# 26-XDS110_DEBUGGER.net
KiCad netlist of a schematic drawn in Altium Designer
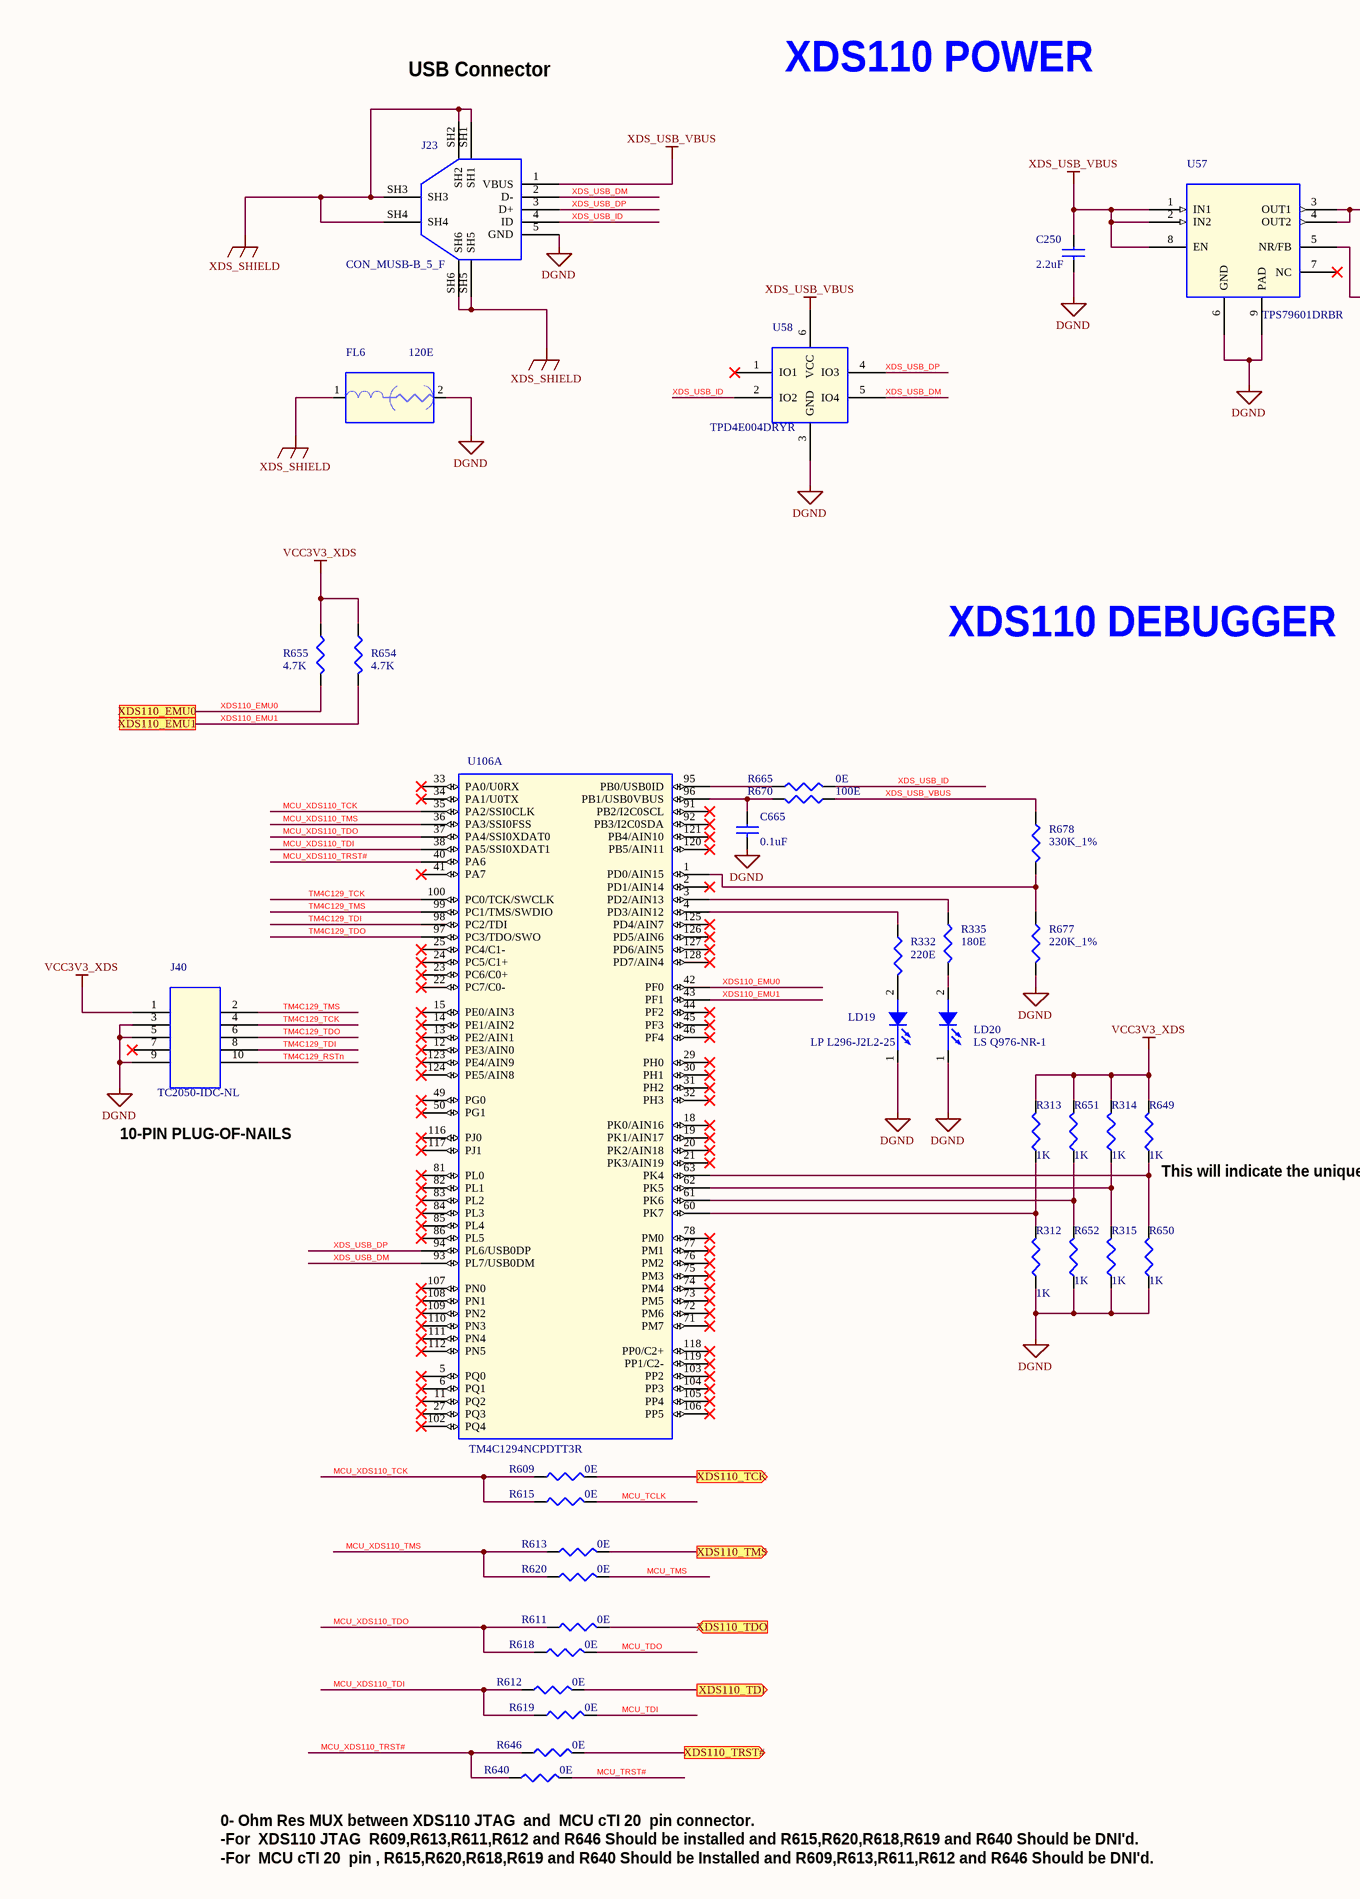
[diagram p0: 26-XDS110 DEBUGGER.SchDoc, left]
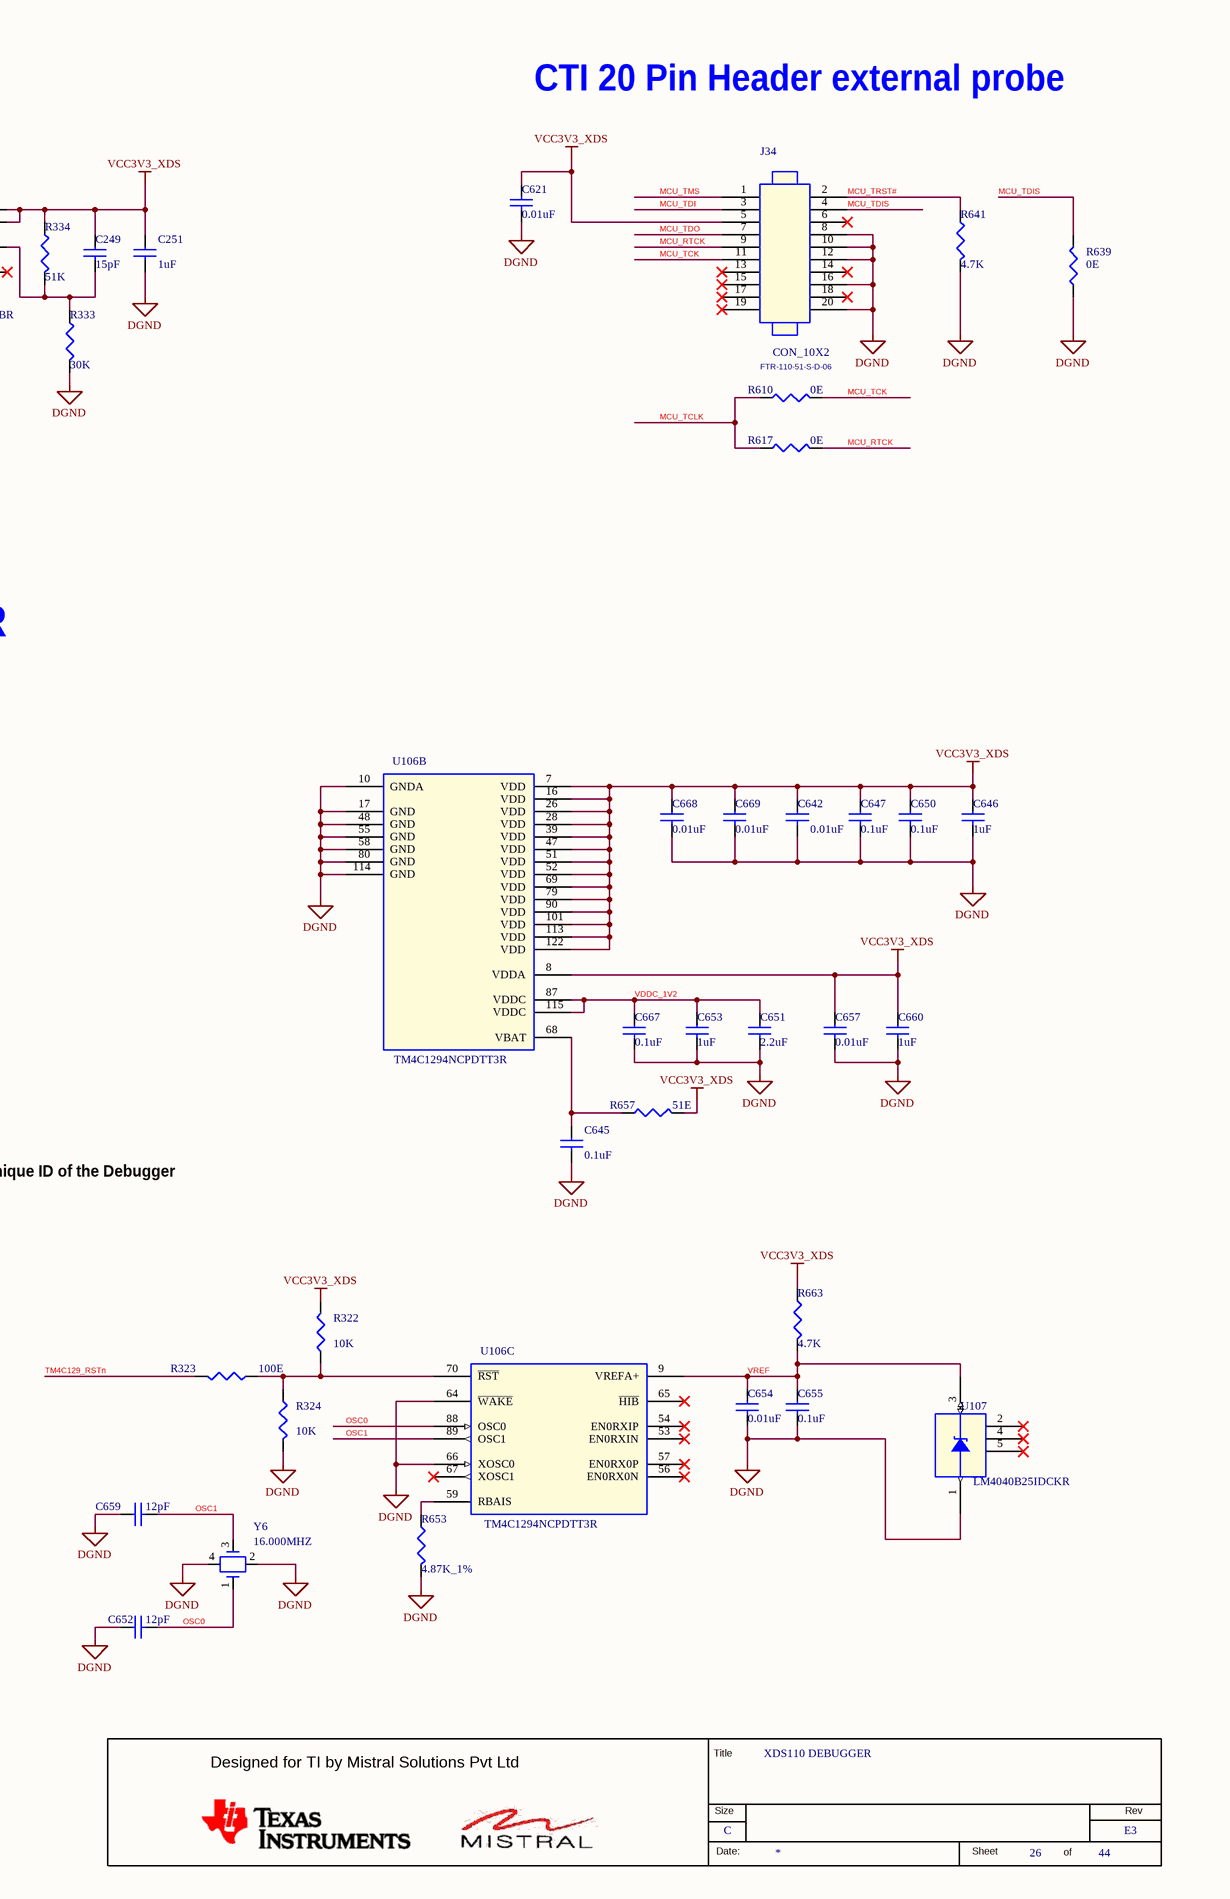
[diagram p1: 26-XDS110 DEBUGGER.SchDoc, right]

(export (version "E")
  (design (tool "Eeschema 10.0.6"))
  (components
    (comp (ref "C249")
      (value "15pF")
      (footprint "CAP0402_0-75")
      (description "CAP CERAMIC 15pF 50V 5% C0G 0402")
      (fields
        (field (name "MISTRAL PART NO") "120010040006-R")
        (field (name "MFR_PART_NUMBER") "GRM1555C1H150JA01D")
      )
      (libsource (lib "*") (part "CAP_Dup5"))
    )
    (comp (ref "C250")
      (value "2.2uF")
      (footprint "CAP0402_0-75")
      (description "CAP CERAMIC 2.2uF 10V 20% X5R 0402")
      (fields
        (field (name "MISTRAL PART NO") "120018010016-R")
        (field (name "MFR_PART_NUMBER") "GRT155R61A225ME01D")
      )
      (libsource (lib "*") (part "CAP_Dup5"))
    )
    (comp (ref "C251")
      (value "1uF")
      (footprint "CAP0402_0-75")
      (description "CAP CERAMIC 1uF 16V 20% X5R 0402")
      (fields (field (name "DISTRIBUTOR_PART_NUMBER") "587-5514-1-ND") (field (name "VOLTAGE") "16V"))
      (libsource (lib "*") (part "CAP_Dup5"))
    )
    (comp (ref "C621")
      (value "0.01uF")
      (footprint "CAP0201_0-5")
      (description "CAP CERAMIC 0.01uF 25V 10% X5R 0201")
      (fields
        (field (name "MISTRAL PART NO") "120018010007-R")
        (field (name "MFR_PART_NUMBER") "GRM033R61E103KA12J")
      )
      (libsource (lib "*") (part "CAP_Dup4"))
    )
    (comp (ref "C642")
      (value "0.01uF")
      (footprint "CAP0201_0-5")
      (description "CAP CERAMIC 0.01uF 25V 10% X5R 0201")
      (fields
        (field (name "MISTRAL PART NO") "120018010007-R")
        (field (name "MFR_PART_NUMBER") "GRM033R61E103KA12J")
      )
      (libsource (lib "*") (part "CAP_Dup5"))
    )
    (comp (ref "C645")
      (value "0.1uF")
      (footprint "CAP0201_0-5")
      (description "CAP CERAMIC 0.1uF 16V 10% X5R 0201")
      (fields (field (name "DISTRIBUTOR_PART_NUMBER") "490-16742-1-ND") (field (name "VOLTAGE") "16V"))
      (libsource (lib "*") (part "CAP_Dup5"))
    )
    (comp (ref "C646")
      (value "1uF")
      (footprint "CAP0402_0-75")
      (description "CAP CERAMIC 1uF 16V 20% X5R 0402")
      (fields
        (field (name "MISTRAL PART NO") "120018020006-R")
        (field (name "MFR_PART_NUMBER") "EMK105BJ105MV-F")
      )
      (libsource (lib "*") (part "CAP_Dup5"))
    )
    (comp (ref "C647")
      (value "0.1uF")
      (footprint "CAP0201_0-5")
      (description "CAP CERAMIC 0.1uF 16V 10% X5R 0201")
      (fields (field (name "DISTRIBUTOR_PART_NUMBER") "490-16742-1-ND") (field (name "VOLTAGE") "16V"))
      (libsource (lib "*") (part "CAP_Dup5"))
    )
    (comp (ref "C650")
      (value "0.1uF")
      (footprint "CAP0201_0-5")
      (description "CAP CERAMIC 0.1uF 16V 10% X5R 0201")
      (fields (field (name "DISTRIBUTOR_PART_NUMBER") "490-16742-1-ND") (field (name "VOLTAGE") "16V"))
      (libsource (lib "*") (part "CAP_Dup5"))
    )
    (comp (ref "C651")
      (value "2.2uF")
      (footprint "CAP0402_0-75")
      (description "CAP CERAMIC 2.2uF 10V 20% X5R 0402")
      (fields
        (field (name "MISTRAL PART NO") "120018010016-R")
        (field (name "MFR_PART_NUMBER") "GRT155R61A225ME01D")
      )
      (libsource (lib "*") (part "CAP_Dup5"))
    )
    (comp (ref "C652")
      (value "12pF")
      (footprint "CAP0402")
      (description "CAP CERAMIC 12pF 50V 5% C0G 0402")
      (fields
        (field (name "MISTRAL PART NO") "120015110024-R")
        (field (name "MFR_PART_NUMBER") "GRM1555C1H120JA01D")
      )
      (libsource (lib "*") (part "CAP_Dup5"))
    )
    (comp (ref "C653")
      (value "1uF")
      (footprint "CAP0402_0-75")
      (description "CAP CERAMIC 1uF 16V 20% X5R 0402")
      (fields (field (name "DISTRIBUTOR_PART_NUMBER") "587-5514-1-ND") (field (name "VOLTAGE") "16V"))
      (libsource (lib "*") (part "CAP_Dup5"))
    )
    (comp (ref "C654")
      (value "0.01uF")
      (footprint "CAP0201_0-5")
      (description "CAP CERAMIC 0.01uF 25V 10% X5R 0201")
      (fields (field (name "DISTRIBUTOR_PART_NUMBER") "GRM033R61E103KA12J-ND") (field (name "VOLTAGE") "25V"))
      (libsource (lib "*") (part "CAP_Dup5"))
    )
    (comp (ref "C655")
      (value "0.1uF")
      (footprint "CAP0201_0-5")
      (description "CAP CERAMIC 0.1uF 16V 10% X5R 0201")
      (fields
        (field (name "MISTRAL PART NO") "120009030072-R")
        (field (name "MFR_PART_NUMBER") "GRM033R61C104KE84J")
      )
      (libsource (lib "*") (part "CAP_Dup5"))
    )
    (comp (ref "C657")
      (value "0.01uF")
      (footprint "CAP0201_0-5")
      (description "CAP CERAMIC 0.01uF 25V 10% X5R 0201")
      (fields (field (name "DISTRIBUTOR_PART_NUMBER") "GRM033R61E103KA12J-ND") (field (name "VOLTAGE") "25V"))
      (libsource (lib "*") (part "CAP_Dup5"))
    )
    (comp (ref "C659")
      (value "12pF")
      (footprint "CAP0402")
      (description "CAP CERAMIC 12pF 50V 5% C0G 0402")
      (fields (field (name "DISTRIBUTOR_PART_NUMBER") "490-5924-1-ND") (field (name "VOLTAGE") "50V"))
      (libsource (lib "*") (part "CAP_Dup5"))
    )
    (comp (ref "C660")
      (value "1uF")
      (footprint "CAP0402_0-75")
      (description "CAP CERAMIC 1uF 16V 20% X5R 0402")
      (fields
        (field (name "MISTRAL PART NO") "120018020006-R")
        (field (name "MFR_PART_NUMBER") "EMK105BJ105MV-F")
      )
      (libsource (lib "*") (part "CAP_Dup5"))
    )
    (comp (ref "C665")
      (value "0.1uF")
      (footprint "CAP0201_0-5")
      (description "CAP CERAMIC 0.1uF 16V 10% X5R 0201")
      (fields (field (name "DISTRIBUTOR_PART_NUMBER") "490-16742-1-ND") (field (name "VOLTAGE") "16V"))
      (libsource (lib "*") (part "CAP_Dup5"))
    )
    (comp (ref "C667")
      (value "0.1uF")
      (footprint "CAP0201_0-5")
      (description "CAP CERAMIC 0.1uF 16V 10% X5R 0201")
      (fields
        (field (name "MISTRAL PART NO") "120009030072-R")
        (field (name "MFR_PART_NUMBER") "GRM033R61C104KE84J")
      )
      (libsource (lib "*") (part "CAP_Dup5"))
    )
    (comp (ref "C668")
      (value "0.01uF")
      (footprint "CAP0201_0-5")
      (description "CAP CERAMIC 0.01uF 25V 10% X5R 0201")
      (fields
        (field (name "MISTRAL PART NO") "120018010007-R")
        (field (name "MFR_PART_NUMBER") "GRM033R61E103KA12J")
      )
      (libsource (lib "*") (part "CAP_Dup5"))
    )
    (comp (ref "C669")
      (value "0.01uF")
      (footprint "CAP0201_0-5")
      (description "CAP CERAMIC 0.01uF 25V 10% X5R 0201")
      (fields (field (name "DISTRIBUTOR_PART_NUMBER") "GRM033R61E103KA12J-ND") (field (name "VOLTAGE") "25V"))
      (libsource (lib "*") (part "CAP_Dup5"))
    )
    (comp (ref "FL6")
      (value "120E")
      (footprint "EMIFIL_BLM15A_0402_0-6")
      (description "FERRITE CHIP 120E 1.3A 0402")
      (fields
        (field (name "MISTRAL PART NO") "130012030043-R")
        (field (name "MFR_PART_NUMBER") "BLM15PD121SN1")
      )
      (libsource (lib "*") (part "EMIFILTER_IND"))
    )
    (comp (ref "J23")
      (value "CON_MUSB-B_5_F")
      (footprint "CON_MUSBB5_1051640001_S_R_S_2-5")
      (description "CON MICRO USB-B TYPE 5POS FEMALE RT SMD")
      (fields (field (name "MISTRAL PART NO") "150017080018-R") (field (name "MFR_PART_NUMBER") "1051640001"))
      (libsource (lib "*") (part "CON_MUSB-B_5_1051640001"))
    )
    (comp (ref "J34")
      (value "CON_10X2")
      (footprint "CON_10X2_FTR-110-51-S-D_P_S_S")
      (description "CON 10X2 1.27MM PITCH MALE SMD")
      (fields
        (field (name "MISTRAL PART NO") "150011090001-R")
        (field (name "MFR_PART_NUMBER") "FTR-110-51-S-D-06")
        (field (name "TOLERANCE") "NA")
      )
      (libsource (lib "*") (part "CON_10X2"))
    )
    (comp (ref "J40")
      (value "TC2050-IDC-NL")
      (footprint "CON_2X5_TC2050-IDC-430-NL_T")
      (description "ACCESSORIE CABLE TAG CONNECT IN CIRCUIT 10POS WITH IDC CONNECTOR")
      (fields (field (name "DISTRIBUTOR_PART_NUMBER") "NA") (field (name "MISTRAL PART NO") "170015120001"))
      (libsource (lib "*") (part "CON_5X2"))
    )
    (comp (ref "LD19")
      (value "LP L296-J2L2-25")
      (footprint "LED_0603_0-7")
      (description "LED PURE GREEN 0603")
      (fields
        (field (name "MISTRAL PART NO") "130017080025-R")
        (field (name "MFR_PART_NUMBER") "LP L296-J2L2-25-Z")
      )
      (libsource (lib "*") (part "DIODE_LED"))
    )
    (comp (ref "LD20")
      (value "LS Q976-NR-1")
      (footprint "LED_0603_0-8")
      (description "LED SUPER RED 0603")
      (fields (field (name "DISTRIBUTOR_PART_NUMBER") "475-2512-1-ND") (field (name "VOLTAGE") "NA"))
      (libsource (lib "*") (part "DIODE_LED"))
    )
    (comp (ref "R312")
      (value "1K")
      (footprint "RES0201")
      (description "RES 1K 1/20W 5% 0201")
      (fields
        (field (name "MISTRAL PART NO") "110015080014-R")
        (field (name "MFR_PART_NUMBER") "CRCW02011K00FKED")
      )
      (libsource (lib "*") (part "RESISTOR_Dup4"))
    )
    (comp (ref "R313")
      (value "1K")
      (footprint "RES0201")
      (description "RES 1K 1/20W 5% 0201")
      (fields (field (name "DISTRIBUTOR_PART_NUMBER") "541-1.00KAABCT-ND") (field (name "VOLTAGE") "NA"))
      (libsource (lib "*") (part "RESISTOR_Dup4"))
    )
    (comp (ref "R314")
      (value "1K")
      (footprint "RES0201")
      (description "RES 1K 1/20W 5% 0201")
      (fields
        (field (name "MISTRAL PART NO") "110015080014-R")
        (field (name "MFR_PART_NUMBER") "CRCW02011K00FKED")
      )
      (libsource (lib "*") (part "RESISTOR_Dup4"))
    )
    (comp (ref "R315")
      (value "1K")
      (footprint "RES0201")
      (description "RES 1K 1/20W 5% 0201")
      (fields (field (name "DISTRIBUTOR_PART_NUMBER") "541-1.00KAABCT-ND") (field (name "VOLTAGE") "NA"))
      (libsource (lib "*") (part "RESISTOR_Dup4"))
    )
    (comp (ref "R322")
      (value "10K")
      (footprint "RES0402_0-5")
      (description "RES 10K 1/16W 5% 0402")
      (fields (field (name "DISTRIBUTOR_PART_NUMBER") "311-10KJRCT-ND") (field (name "VOLTAGE") "NA"))
      (libsource (lib "*") (part "RESISTOR_Dup5"))
    )
    (comp (ref "R323")
      (value "100E")
      (footprint "RES0402_0-5")
      (description "RES 100E 1/16W 5% 0402")
      (fields (field (name "DISTRIBUTOR_PART_NUMBER") "541-100JCT-ND") (field (name "VOLTAGE") "NA"))
      (libsource (lib "*") (part "RESISTOR_Dup5"))
    )
    (comp (ref "R324")
      (value "10K")
      (footprint "RES0402_0-5")
      (description "RES 10K 1/16W 5% 0402")
      (fields
        (field (name "MISTRAL PART NO") "110009030208-R")
        (field (name "MFR_PART_NUMBER") "RC0402JR-0710KL")
      )
      (libsource (lib "*") (part "RESISTOR_Dup5"))
    )
    (comp (ref "R332")
      (value "220E")
      (footprint "RES0402_0-5")
      (description "RES 220E 1/16W 5% 0402")
      (fields (field (name "VOLTAGE") "NA") (field (name "DISTRIBUTOR_PART_NUMBER") "P220JCT-ND"))
      (libsource (lib "*") (part "RESISTOR_Dup5"))
    )
    (comp (ref "R333")
      (value "30K")
      (footprint "RES0402_0-5")
      (description "RES 30K 1/16W 5% 0402")
      (fields
        (field (name "MISTRAL PART NO") "110017080023-R")
        (field (name "MFR_PART_NUMBER") "CRCW040230K0JNED")
      )
      (libsource (lib "*") (part "RESISTOR_Dup5"))
    )
    (comp (ref "R334")
      (value "51K")
      (footprint "RES0402_0-5")
      (description "RES 51K 1/16W 5% 0402")
      (fields
        (field (name "MISTRAL PART NO") "110009030966-R")
        (field (name "MFR_PART_NUMBER") "CRCW040251K0JNED")
      )
      (libsource (lib "*") (part "RESISTOR_Dup5"))
    )
    (comp (ref "R335")
      (value "180E")
      (footprint "RES0402")
      (description "RES 180E 1/16W 5% 0402")
      (fields
        (field (name "MISTRAL PART NO") "110009030371-R")
        (field (name "MFR_PART_NUMBER") "ERJ-2GEJ181X")
      )
      (libsource (lib "*") (part "RESISTOR_Dup5"))
    )
    (comp (ref "R609")
      (value "0E")
      (footprint "RES0402_0-5")
      (description "RES 0E 1/16W 0402")
      (fields (field (name "DISTRIBUTOR_PART_NUMBER") "541-0.0JCT-ND") (field (name "VOLTAGE") "NA"))
      (libsource (lib "*") (part "RESISTOR_Dup4"))
    )
    (comp (ref "R610")
      (value "0E")
      (footprint "RES0402_0-5")
      (description "RES 0E 1/16W 0402")
      (fields (field (name "DISTRIBUTOR_PART_NUMBER") "541-0.0JCT-ND") (field (name "VOLTAGE") "NA"))
      (libsource (lib "*") (part "RESISTOR_Dup4"))
    )
    (comp (ref "R611")
      (value "0E")
      (footprint "RES0402_0-5")
      (description "RES 0E 1/16W 0402")
      (fields
        (field (name "MISTRAL PART NO") "110010080019-P")
        (field (name "MFR_PART_NUMBER") "CRCW04020000Z0ED")
      )
      (libsource (lib "*") (part "RESISTOR_Dup4"))
    )
    (comp (ref "R612")
      (value "0E")
      (footprint "RES0402_0-5")
      (description "RES 0E 1/16W 0402")
      (fields
        (field (name "MISTRAL PART NO") "110010080019-P")
        (field (name "MFR_PART_NUMBER") "CRCW04020000Z0ED")
      )
      (libsource (lib "*") (part "RESISTOR_Dup4"))
    )
    (comp (ref "R613")
      (value "0E")
      (footprint "RES0402_0-5")
      (description "RES 0E 1/16W 0402")
      (fields
        (field (name "MISTRAL PART NO") "110010080019-P")
        (field (name "MFR_PART_NUMBER") "CRCW04020000Z0ED")
      )
      (libsource (lib "*") (part "RESISTOR_Dup4"))
    )
    (comp (ref "R615")
      (value "0E")
      (footprint "RES0402_0-5")
      (description "RES 0E 1/16W 0402")
      (fields (field (name "DISTRIBUTOR_PART_NUMBER") "541-0.0JCT-ND") (field (name "VOLTAGE") "NA"))
      (libsource (lib "*") (part "RESISTOR_Dup4"))
    )
    (comp (ref "R617")
      (value "0E")
      (footprint "RES0402_0-5")
      (description "RES 0E 1/16W 0402")
      (fields
        (field (name "MISTRAL PART NO") "110010080019-P")
        (field (name "MFR_PART_NUMBER") "CRCW04020000Z0ED")
      )
      (libsource (lib "*") (part "RESISTOR_Dup4"))
    )
    (comp (ref "R618")
      (value "0E")
      (footprint "RES0402_0-5")
      (description "RES 0E 1/16W 0402")
      (fields (field (name "DISTRIBUTOR_PART_NUMBER") "541-0.0JCT-ND") (field (name "VOLTAGE") "NA"))
      (libsource (lib "*") (part "RESISTOR_Dup4"))
    )
    (comp (ref "R619")
      (value "0E")
      (footprint "RES0402_0-5")
      (description "RES 0E 1/16W 0402")
      (fields
        (field (name "MISTRAL PART NO") "110010080019-P")
        (field (name "MFR_PART_NUMBER") "CRCW04020000Z0ED")
      )
      (libsource (lib "*") (part "RESISTOR_Dup4"))
    )
    (comp (ref "R620")
      (value "0E")
      (footprint "RES0402_0-5")
      (description "RES 0E 1/16W 0402")
      (fields
        (field (name "MISTRAL PART NO") "110010080019-P")
        (field (name "MFR_PART_NUMBER") "CRCW04020000Z0ED")
      )
      (libsource (lib "*") (part "RESISTOR_Dup4"))
    )
    (comp (ref "R639")
      (value "0E")
      (footprint "RES0402_0-5")
      (description "RES 0E 1/16W 0402")
      (fields
        (field (name "MISTRAL PART NO") "110010080019-P")
        (field (name "MFR_PART_NUMBER") "CRCW04020000Z0ED")
      )
      (libsource (lib "*") (part "RESISTOR_Dup4"))
    )
    (comp (ref "R640")
      (value "0E")
      (footprint "RES0402_0-5")
      (description "RES 0E 1/16W 0402")
      (fields (field (name "DISTRIBUTOR_PART_NUMBER") "541-0.0JCT-ND") (field (name "VOLTAGE") "NA"))
      (libsource (lib "*") (part "RESISTOR_Dup4"))
    )
    (comp (ref "R641")
      (value "4.7K")
      (footprint "RES0402")
      (description "RES 4.7K 1/16W 5% 0402")
      (fields
        (field (name "MISTRAL PART NO") "110009030792-R")
        (field (name "MFR_PART_NUMBER") "RC0402JR-074K7L")
      )
      (libsource (lib "*") (part "RESISTOR_Dup3"))
    )
    (comp (ref "R646")
      (value "0E")
      (footprint "RES0402_0-5")
      (description "RES 0E 1/16W 0402")
      (fields
        (field (name "MISTRAL PART NO") "110010080019-P")
        (field (name "MFR_PART_NUMBER") "CRCW04020000Z0ED")
      )
      (libsource (lib "*") (part "RESISTOR_Dup4"))
    )
    (comp (ref "R649")
      (value "1K")
      (footprint "RES0201")
      (description "RES 1K 1/20W 5% 0201")
      (fields (field (name "DISTRIBUTOR_PART_NUMBER") "541-1.00KAABCT-ND") (field (name "VOLTAGE") "NA"))
      (libsource (lib "*") (part "RESISTOR_Dup4"))
    )
    (comp (ref "R650")
      (value "1K")
      (footprint "RES0201")
      (description "RES 1K 1/20W 5% 0201")
      (fields
        (field (name "MISTRAL PART NO") "110015080014-R")
        (field (name "MFR_PART_NUMBER") "CRCW02011K00FKED")
      )
      (libsource (lib "*") (part "RESISTOR_Dup4"))
    )
    (comp (ref "R651")
      (value "1K")
      (footprint "RES0201")
      (description "RES 1K 1/20W 5% 0201")
      (fields (field (name "DISTRIBUTOR_PART_NUMBER") "541-1.00KAABCT-ND") (field (name "VOLTAGE") "NA"))
      (libsource (lib "*") (part "RESISTOR_Dup4"))
    )
    (comp (ref "R652")
      (value "1K")
      (footprint "RES0201")
      (description "RES 1K 1/20W 5% 0201")
      (fields (field (name "DISTRIBUTOR_PART_NUMBER") "541-1.00KAABCT-ND") (field (name "VOLTAGE") "NA"))
      (libsource (lib "*") (part "RESISTOR_Dup4"))
    )
    (comp (ref "R653")
      (value "4.87K_1%")
      (footprint "RES0402")
      (description "RES 4.87K 1/16W 1% 0402")
      (fields
        (field (name "MISTRAL PART NO") "110009030803-R")
        (field (name "MFR_PART_NUMBER") "ERJ2RKF4871X")
      )
      (libsource (lib "*") (part "RESISTOR_Dup5"))
    )
    (comp (ref "R654")
      (value "4.7K")
      (footprint "RES0402")
      (description "RES 4.7K 1/16W 5% 0402")
      (fields (field (name "DISTRIBUTOR_PART_NUMBER") "311-4.7KJRCT-ND") (field (name "VOLTAGE") "NA"))
      (libsource (lib "*") (part "RESISTOR_Dup3"))
    )
    (comp (ref "R655")
      (value "4.7K")
      (footprint "RES0402")
      (description "RES 4.7K 1/16W 5% 0402")
      (fields
        (field (name "MISTRAL PART NO") "110009030792-R")
        (field (name "MFR_PART_NUMBER") "RC0402JR-074K7L")
      )
      (libsource (lib "*") (part "RESISTOR_Dup3"))
    )
    (comp (ref "R657")
      (value "51E")
      (footprint "RES0402")
      (description "RES 51E 1/16W 5% 0402")
      (fields (field (name "DISTRIBUTOR_PART_NUMBER") "P51JTR-ND") (field (name "TOLERANCE") "5%"))
      (libsource (lib "*") (part "RESISTOR_Dup5"))
    )
    (comp (ref "R663")
      (value "4.7K")
      (footprint "RES0402")
      (description "RES 4.7K 1/16W 5% 0402")
      (fields
        (field (name "MISTRAL PART NO") "110009030792-R")
        (field (name "MFR_PART_NUMBER") "RC0402JR-074K7L")
      )
      (libsource (lib "*") (part "RESISTOR_Dup3"))
    )
    (comp (ref "R665")
      (value "0E")
      (footprint "RES0402_0-5")
      (description "RES 0E 1/16W 0402")
      (fields (field (name "DISTRIBUTOR_PART_NUMBER") "541-0.0JCT-ND") (field (name "VOLTAGE") "NA"))
      (libsource (lib "*") (part "RESISTOR_Dup4"))
    )
    (comp (ref "R670")
      (value "100E")
      (footprint "RES0402_0-5")
      (description "RES 100E 1/16W 5% 0402")
      (fields (field (name "DISTRIBUTOR_PART_NUMBER") "541-100JCT-ND") (field (name "VOLTAGE") "NA"))
      (libsource (lib "*") (part "RESISTOR_Dup5"))
    )
    (comp (ref "R677")
      (value "220K_1%")
      (footprint "RES0402_0-5")
      (description "RES 220K 1/16W 1% 0402")
      (fields (field (name "DISTRIBUTOR_PART_NUMBER") "541-220KLCT-ND") (field (name "VOLTAGE") "NA"))
      (libsource (lib "*") (part "RESISTOR_Dup5"))
    )
    (comp (ref "R678")
      (value "330K_1%")
      (footprint "RES0402_0-5")
      (description "RES 330K 1/16W 1% 0402")
      (fields (field (name "DISTRIBUTOR_PART_NUMBER") "541-330KLCT-ND") (field (name "VOLTAGE") "NA"))
      (libsource (lib "*") (part "RESISTOR_Dup5"))
    )
    (comp (ref "U57")
      (value "TPS79601DRBR")
      (footprint "SON8_25-59_130X130_1")
      (description "IC 1A HIGH PSRR RF ADJ LDO LINEAR REGULATOR SON8")
      (fields
        (field (name "VOLTAGE") "NA")
        (field (name "MISTRAL PART NO") "142009080012-R")
        (field (name "LIBRARY PATH") "Y~{:}MIS_DATABAS~{E}Librar~{y}ALTIUM_TOO~{L}SCHEMATICS_PART~{S}MS_MISCPOWER_Library.schlib")
      )
      (libsource (lib "*") (part "TPS79601DRBR_SON8"))
    )
    (comp (ref "U58")
      (value "TPD4E004DRYR")
      (footprint "SON6_19-68_60X45")
      (description "IC 4CH ESD-PROT ARRAY SON6")
      (fields
        (field (name "MISTRAL PART NO") "141010020012-P")
        (field (name "DISTRIBUTOR_PART_NUMBER") "296-23618-1-ND")
      )
      (libsource (lib "*") (part "TPD4E004_SON6"))
    )
    (comp (ref "U106")
      (value "TM4C1294NCPDTT3R")
      (footprint "TQFP128_15-74_550X550_1-2")
      (description "IC 32-BIT MICROCONTROLLER WITH 1MB FLASH TQFP128")
      (fields
        (field (name "DISTRIBUTOR_PART_NUMBER") "TM4C1294NCPDTT3R-ND")
        (field (name "VOLTAGE") "NA")
        (field (name "MISTRAL PART NO") "141217080002-R")
        (field (name "TOLERANCE") "NA")
      )
      (libsource (lib "*") (part "TM4C1294NCPDTT3R_TQFP128"))
    )
    (comp (ref "U107")
      (value "LM4040B25IDCKR")
      (footprint "SC70-5_1-1")
      (description "IC PRECISION MICROPOWER SHUNT VOLTAGE REFERENCE SC70-5")
      (fields (field (name "DISTRIBUTOR_PART_NUMBER") "296-20873-1-ND") (field (name "VOLTAGE") "NA"))
      (libsource (lib "*") (part "LM4040B25IDCKR_SC70-5"))
    )
    (comp (ref "Y6")
      (value "16.000MHZ")
      (footprint "XTAL4_NX3225GA_130X100_SMD_0-9")
      (description "CRY 16.000MHz SMD")
      (fields
        (field (name "MISTRAL PART NO") "130017080024-R")
        (field (name "MFR_PART_NUMBER") "NX3225GA-16.000M-STD-CRG-1")
      )
      (libsource (lib "*") (part "CRY4_13"))
    )
  )
  (nets
    (net (code "1") (name "/MCU_RTCK") (class "Default")
      (node (ref "J34") (pin "9") (pinfunction "9_9") (pintype "passive"))
      (node (ref "R617") (pin "2") (pinfunction "2_2") (pintype "passive"))
    )
    (net (code "2") (name "/MCU_TCK") (class "Default")
      (node (ref "J34") (pin "11") (pinfunction "11_11") (pintype "passive"))
      (node (ref "R610") (pin "2") (pinfunction "2_2") (pintype "passive"))
    )
    (net (code "3") (name "/MCU_TCLK") (class "Default")
      (node (ref "R610") (pin "1") (pinfunction "1_1") (pintype "passive"))
      (node (ref "R615") (pin "2") (pinfunction "2_2") (pintype "passive"))
      (node (ref "R617") (pin "1") (pinfunction "1_1") (pintype "passive"))
    )
    (net (code "4") (name "/MCU_TDI") (class "Default")
      (node (ref "J34") (pin "3") (pinfunction "3_3") (pintype "passive"))
      (node (ref "R619") (pin "2") (pinfunction "2_2") (pintype "passive"))
    )
    (net (code "5") (name "/MCU_TDIS") (class "Default")
      (node (ref "J34") (pin "4") (pinfunction "4_4") (pintype "passive"))
      (node (ref "R639") (pin "2") (pinfunction "2_2") (pintype "passive"))
    )
    (net (code "6") (name "/MCU_TDO") (class "Default")
      (node (ref "J34") (pin "7") (pinfunction "7_7") (pintype "passive"))
      (node (ref "R618") (pin "2") (pinfunction "2_2") (pintype "passive"))
    )
    (net (code "7") (name "/MCU_TMS") (class "Default")
      (node (ref "J34") (pin "1") (pinfunction "1_1") (pintype "passive"))
      (node (ref "R620") (pin "2") (pinfunction "2_2") (pintype "passive"))
    )
    (net (code "8") (name "/MCU_TRST#") (class "Default")
      (node (ref "J34") (pin "2") (pinfunction "2_2") (pintype "passive"))
      (node (ref "R640") (pin "2") (pinfunction "2_2") (pintype "passive"))
      (node (ref "R641") (pin "1") (pinfunction "1_1") (pintype "passive"))
    )
    (net (code "9") (name "/MCU_XDS110_TCK") (class "Default")
      (node (ref "R609") (pin "1") (pinfunction "1_1") (pintype "passive"))
      (node (ref "R615") (pin "1") (pinfunction "1_1") (pintype "passive"))
      (node (ref "U106") (pin "35") (pinfunction "PA2/SSI0CLK_35") (pintype "bidirectional"))
    )
    (net (code "10") (name "/MCU_XDS110_TDI") (class "Default")
      (node (ref "R612") (pin "1") (pinfunction "1_1") (pintype "passive"))
      (node (ref "R619") (pin "1") (pinfunction "1_1") (pintype "passive"))
      (node (ref "U106") (pin "38") (pinfunction "PA5/SSI0XDAT1_38") (pintype "bidirectional"))
    )
    (net (code "11") (name "/MCU_XDS110_TDO") (class "Default")
      (node (ref "R611") (pin "1") (pinfunction "1_1") (pintype "passive"))
      (node (ref "R618") (pin "1") (pinfunction "1_1") (pintype "passive"))
      (node (ref "U106") (pin "37") (pinfunction "PA4/SSI0XDAT0_37") (pintype "bidirectional"))
    )
    (net (code "12") (name "/MCU_XDS110_TMS") (class "Default")
      (node (ref "R613") (pin "1") (pinfunction "1_1") (pintype "passive"))
      (node (ref "R620") (pin "1") (pinfunction "1_1") (pintype "passive"))
      (node (ref "U106") (pin "36") (pinfunction "PA3/SSI0FSS_36") (pintype "bidirectional"))
    )
    (net (code "13") (name "/MCU_XDS110_TRST#") (class "Default")
      (node (ref "R640") (pin "1") (pinfunction "1_1") (pintype "passive"))
      (node (ref "R646") (pin "1") (pinfunction "1_1") (pintype "passive"))
      (node (ref "U106") (pin "40") (pinfunction "PA6_40") (pintype "bidirectional"))
    )
    (net (code "14") (name "/OSC0") (class "Default")
      (node (ref "C652") (pin "2") (pinfunction "2_2") (pintype "passive"))
      (node (ref "U106") (pin "88") (pinfunction "OSC0_88") (pintype "input"))
      (node (ref "Y6") (pin "1") (pinfunction "1_1") (pintype "passive"))
    )
    (net (code "15") (name "/OSC1") (class "Default")
      (node (ref "C659") (pin "2") (pinfunction "2_2") (pintype "passive"))
      (node (ref "U106") (pin "89") (pinfunction "OSC1_89") (pintype "output"))
      (node (ref "Y6") (pin "3") (pinfunction "3_3") (pintype "passive"))
    )
    (net (code "16") (name "/TM4C129_RSTn") (class "Default")
      (node (ref "J40") (pin "10") (pinfunction "10_10") (pintype "passive"))
      (node (ref "R323") (pin "2") (pinfunction "2_2") (pintype "passive"))
    )
    (net (code "17") (name "/TM4C129_TCK") (class "Default")
      (node (ref "J40") (pin "4") (pinfunction "4_4") (pintype "passive"))
      (node (ref "U106") (pin "100") (pinfunction "PC0/TCK/SWCLK_100") (pintype "bidirectional"))
    )
    (net (code "18") (name "/TM4C129_TDI") (class "Default")
      (node (ref "J40") (pin "8") (pinfunction "8_8") (pintype "passive"))
      (node (ref "U106") (pin "98") (pinfunction "PC2/TDI_98") (pintype "bidirectional"))
    )
    (net (code "19") (name "/TM4C129_TDO") (class "Default")
      (node (ref "J40") (pin "6") (pinfunction "6_6") (pintype "passive"))
      (node (ref "U106") (pin "97") (pinfunction "PC3/TDO/SWO_97") (pintype "bidirectional"))
    )
    (net (code "20") (name "/TM4C129_TMS") (class "Default")
      (node (ref "J40") (pin "2") (pinfunction "2_2") (pintype "passive"))
      (node (ref "U106") (pin "99") (pinfunction "PC1/TMS/SWDIO_99") (pintype "bidirectional"))
    )
    (net (code "21") (name "/VDDC_1V2") (class "Default")
      (node (ref "C651") (pin "1") (pinfunction "1_1") (pintype "passive"))
      (node (ref "C653") (pin "1") (pinfunction "1_1") (pintype "passive"))
      (node (ref "C667") (pin "1") (pinfunction "1_1") (pintype "passive"))
      (node (ref "U106") (pin "115") (pinfunction "VDDC_115") (pintype "power_in"))
      (node (ref "U106") (pin "87") (pinfunction "VDDC_87") (pintype "power_in"))
    )
    (net (code "22") (name "/VREF") (class "Default")
      (node (ref "C654") (pin "1") (pinfunction "1_1") (pintype "passive"))
      (node (ref "C655") (pin "1") (pinfunction "1_1") (pintype "passive"))
      (node (ref "R663") (pin "2") (pinfunction "2_2") (pintype "passive"))
      (node (ref "U106") (pin "9") (pinfunction "VREFA+_9") (pintype "passive"))
      (node (ref "U107") (pin "3") (pinfunction "CATHODE_3") (pintype "bidirectional"))
    )
    (net (code "23") (name "/XDS110_EMU0") (class "Default")
      (node (ref "R655") (pin "2") (pinfunction "2_2") (pintype "passive"))
      (node (ref "U106") (pin "42") (pinfunction "PF0_42") (pintype "bidirectional"))
    )
    (net (code "24") (name "/XDS110_EMU1") (class "Default")
      (node (ref "R654") (pin "2") (pinfunction "2_2") (pintype "passive"))
      (node (ref "U106") (pin "43") (pinfunction "PF1_43") (pintype "bidirectional"))
    )
    (net (code "25") (name "/XDS110_TCK") (class "Default")
      (node (ref "R609") (pin "2") (pinfunction "2_2") (pintype "passive"))
    )
    (net (code "26") (name "/XDS110_TDI") (class "Default")
      (node (ref "R612") (pin "2") (pinfunction "2_2") (pintype "passive"))
    )
    (net (code "27") (name "/XDS110_TDO") (class "Default")
      (node (ref "R611") (pin "2") (pinfunction "2_2") (pintype "passive"))
    )
    (net (code "28") (name "/XDS110_TMS") (class "Default")
      (node (ref "R613") (pin "2") (pinfunction "2_2") (pintype "passive"))
    )
    (net (code "29") (name "/XDS110_TRST#") (class "Default")
      (node (ref "R646") (pin "2") (pinfunction "2_2") (pintype "passive"))
    )
    (net (code "30") (name "/XDS_USB_DM") (class "Default")
      (node (ref "J23") (pin "2") (pinfunction "D-_2") (pintype "passive"))
      (node (ref "U106") (pin "93") (pinfunction "PL7/USB0DM_93") (pintype "bidirectional"))
      (node (ref "U58") (pin "5") (pinfunction "IO4_5") (pintype "passive"))
    )
    (net (code "31") (name "/XDS_USB_DP") (class "Default")
      (node (ref "J23") (pin "3") (pinfunction "D+_3") (pintype "passive"))
      (node (ref "U106") (pin "94") (pinfunction "PL6/USB0DP_94") (pintype "bidirectional"))
      (node (ref "U58") (pin "4") (pinfunction "IO3_4") (pintype "passive"))
    )
    (net (code "32") (name "/XDS_USB_ID") (class "Default")
      (node (ref "J23") (pin "4") (pinfunction "ID_4") (pintype "passive"))
      (node (ref "R665") (pin "2") (pinfunction "2_2") (pintype "passive"))
      (node (ref "U58") (pin "2") (pinfunction "IO2_2") (pintype "passive"))
    )
    (net (code "33") (name "DGND") (class "Default")
      (node (ref "C250") (pin "2") (pinfunction "2_2") (pintype "passive"))
      (node (ref "C251") (pin "2") (pinfunction "2_2") (pintype "passive"))
      (node (ref "C621") (pin "2") (pinfunction "2_2") (pintype "passive"))
      (node (ref "C642") (pin "2") (pinfunction "2_2") (pintype "passive"))
      (node (ref "C645") (pin "2") (pinfunction "2_2") (pintype "passive"))
      (node (ref "C646") (pin "2") (pinfunction "2_2") (pintype "passive"))
      (node (ref "C647") (pin "2") (pinfunction "2_2") (pintype "passive"))
      (node (ref "C650") (pin "2") (pinfunction "2_2") (pintype "passive"))
      (node (ref "C651") (pin "2") (pinfunction "2_2") (pintype "passive"))
      (node (ref "C652") (pin "1") (pinfunction "1_1") (pintype "passive"))
      (node (ref "C653") (pin "2") (pinfunction "2_2") (pintype "passive"))
      (node (ref "C654") (pin "2") (pinfunction "2_2") (pintype "passive"))
      (node (ref "C655") (pin "2") (pinfunction "2_2") (pintype "passive"))
      (node (ref "C657") (pin "2") (pinfunction "2_2") (pintype "passive"))
      (node (ref "C659") (pin "1") (pinfunction "1_1") (pintype "passive"))
      (node (ref "C660") (pin "2") (pinfunction "2_2") (pintype "passive"))
      (node (ref "C665") (pin "2") (pinfunction "2_2") (pintype "passive"))
      (node (ref "C667") (pin "2") (pinfunction "2_2") (pintype "passive"))
      (node (ref "C668") (pin "2") (pinfunction "2_2") (pintype "passive"))
      (node (ref "C669") (pin "2") (pinfunction "2_2") (pintype "passive"))
      (node (ref "FL6") (pin "2") (pinfunction "2_2") (pintype "passive"))
      (node (ref "J23") (pin "5") (pinfunction "GND_5") (pintype "power_in"))
      (node (ref "J34") (pin "10") (pinfunction "10_10") (pintype "passive"))
      (node (ref "J34") (pin "12") (pinfunction "12_12") (pintype "passive"))
      (node (ref "J34") (pin "16") (pinfunction "16_16") (pintype "passive"))
      (node (ref "J34") (pin "20") (pinfunction "20_20") (pintype "passive"))
      (node (ref "J34") (pin "8") (pinfunction "8_8") (pintype "passive"))
      (node (ref "J40") (pin "3") (pinfunction "3_3") (pintype "passive"))
      (node (ref "J40") (pin "5") (pinfunction "5_5") (pintype "passive"))
      (node (ref "J40") (pin "9") (pinfunction "9_9") (pintype "passive"))
      (node (ref "LD19") (pin "1") (pinfunction "CATHODE_1") (pintype "passive"))
      (node (ref "LD20") (pin "1") (pinfunction "CATHODE_1") (pintype "passive"))
      (node (ref "R312") (pin "1") (pinfunction "1_1") (pintype "passive"))
      (node (ref "R315") (pin "1") (pinfunction "1_1") (pintype "passive"))
      (node (ref "R324") (pin "2") (pinfunction "2_2") (pintype "passive"))
      (node (ref "R333") (pin "2") (pinfunction "2_2") (pintype "passive"))
      (node (ref "R639") (pin "1") (pinfunction "1_1") (pintype "passive"))
      (node (ref "R641") (pin "2") (pinfunction "2_2") (pintype "passive"))
      (node (ref "R650") (pin "1") (pinfunction "1_1") (pintype "passive"))
      (node (ref "R652") (pin "1") (pinfunction "1_1") (pintype "passive"))
      (node (ref "R653") (pin "2") (pinfunction "2_2") (pintype "passive"))
      (node (ref "R677") (pin "2") (pinfunction "2_2") (pintype "passive"))
      (node (ref "U106") (pin "10") (pinfunction "GNDA_10") (pintype "power_in"))
      (node (ref "U106") (pin "114") (pinfunction "GND_114") (pintype "power_in"))
      (node (ref "U106") (pin "17") (pinfunction "GND_17") (pintype "power_in"))
      (node (ref "U106") (pin "48") (pinfunction "GND_48") (pintype "power_in"))
      (node (ref "U106") (pin "55") (pinfunction "GND_55") (pintype "power_in"))
      (node (ref "U106") (pin "58") (pinfunction "GND_58") (pintype "power_in"))
      (node (ref "U106") (pin "64") (pinfunction "~{WAKE}_64") (pintype "passive"))
      (node (ref "U106") (pin "66") (pinfunction "XOSC0_66") (pintype "input"))
      (node (ref "U106") (pin "80") (pinfunction "GND_80") (pintype "power_in"))
      (node (ref "U107") (pin "1") (pinfunction "ANODE_1") (pintype "output"))
      (node (ref "U57") (pin "6") (pinfunction "GND_6") (pintype "power_in"))
      (node (ref "U57") (pin "9") (pinfunction "PAD_9") (pintype "power_in"))
      (node (ref "U58") (pin "3") (pinfunction "GND_3") (pintype "power_in"))
      (node (ref "Y6") (pin "2") (pinfunction "2_2") (pintype "passive"))
      (node (ref "Y6") (pin "4") (pinfunction "4_4") (pintype "passive"))
    )
    (net (code "34") (name "Net-(LD19-ANODE)") (class "Default")
      (node (ref "LD19") (pin "2") (pinfunction "ANODE_2") (pintype "passive"))
      (node (ref "R332") (pin "2") (pinfunction "2_2") (pintype "passive"))
    )
    (net (code "35") (name "Net-(LD20-ANODE)") (class "Default")
      (node (ref "LD20") (pin "2") (pinfunction "ANODE_2") (pintype "passive"))
      (node (ref "R335") (pin "2") (pinfunction "2_2") (pintype "passive"))
    )
    (net (code "36") (name "Net-(U57-NR{slash}FB)") (class "Default")
      (node (ref "C249") (pin "2") (pinfunction "2_2") (pintype "passive"))
      (node (ref "R333") (pin "1") (pinfunction "1_1") (pintype "passive"))
      (node (ref "R334") (pin "2") (pinfunction "2_2") (pintype "passive"))
      (node (ref "U57") (pin "5") (pinfunction "NR/FB_5") (pintype "passive"))
    )
    (net (code "37") (name "Net-(U106A-PB0{slash}USB0ID)") (class "Default")
      (node (ref "R665") (pin "1") (pinfunction "1_1") (pintype "passive"))
      (node (ref "U106") (pin "95") (pinfunction "PB0/USB0ID_95") (pintype "bidirectional"))
    )
    (net (code "38") (name "Net-(U106A-PB1{slash}USB0VBUS)") (class "Default")
      (node (ref "C665") (pin "1") (pinfunction "1_1") (pintype "passive"))
      (node (ref "R670") (pin "2") (pinfunction "2_2") (pintype "passive"))
      (node (ref "U106") (pin "96") (pinfunction "PB1/USB0VBUS_96") (pintype "bidirectional"))
    )
    (net (code "39") (name "Net-(U106A-PD0{slash}AIN15)") (class "Default")
      (node (ref "R677") (pin "1") (pinfunction "1_1") (pintype "passive"))
      (node (ref "R678") (pin "2") (pinfunction "2_2") (pintype "passive"))
      (node (ref "U106") (pin "1") (pinfunction "PD0/AIN15_1") (pintype "bidirectional"))
    )
    (net (code "40") (name "Net-(U106A-PD2{slash}AIN13)") (class "Default")
      (node (ref "R335") (pin "1") (pinfunction "1_1") (pintype "passive"))
      (node (ref "U106") (pin "3") (pinfunction "PD2/AIN13_3") (pintype "bidirectional"))
    )
    (net (code "41") (name "Net-(U106A-PD3{slash}AIN12)") (class "Default")
      (node (ref "R332") (pin "1") (pinfunction "1_1") (pintype "passive"))
      (node (ref "U106") (pin "4") (pinfunction "PD3/AIN12_4") (pintype "bidirectional"))
    )
    (net (code "42") (name "Net-(U106A-PK4)") (class "Default")
      (node (ref "R649") (pin "1") (pinfunction "1_1") (pintype "passive"))
      (node (ref "R650") (pin "2") (pinfunction "2_2") (pintype "passive"))
      (node (ref "U106") (pin "63") (pinfunction "PK4_63") (pintype "bidirectional"))
    )
    (net (code "43") (name "Net-(U106A-PK5)") (class "Default")
      (node (ref "R314") (pin "1") (pinfunction "1_1") (pintype "passive"))
      (node (ref "R315") (pin "2") (pinfunction "2_2") (pintype "passive"))
      (node (ref "U106") (pin "62") (pinfunction "PK5_62") (pintype "bidirectional"))
    )
    (net (code "44") (name "Net-(U106A-PK6)") (class "Default")
      (node (ref "R651") (pin "1") (pinfunction "1_1") (pintype "passive"))
      (node (ref "R652") (pin "2") (pinfunction "2_2") (pintype "passive"))
      (node (ref "U106") (pin "61") (pinfunction "PK6_61") (pintype "bidirectional"))
    )
    (net (code "45") (name "Net-(U106A-PK7)") (class "Default")
      (node (ref "R312") (pin "2") (pinfunction "2_2") (pintype "passive"))
      (node (ref "R313") (pin "1") (pinfunction "1_1") (pintype "passive"))
      (node (ref "U106") (pin "60") (pinfunction "PK7_60") (pintype "bidirectional"))
    )
    (net (code "46") (name "Net-(U106B-VBAT)") (class "Default")
      (node (ref "C645") (pin "1") (pinfunction "1_1") (pintype "passive"))
      (node (ref "R657") (pin "1") (pinfunction "1_1") (pintype "passive"))
      (node (ref "U106") (pin "68") (pinfunction "VBAT_68") (pintype "power_in"))
    )
    (net (code "47") (name "Net-(U106C-RBAIS)") (class "Default")
      (node (ref "R653") (pin "1") (pinfunction "1_1") (pintype "passive"))
      (node (ref "U106") (pin "59") (pinfunction "RBAIS_59") (pintype "passive"))
    )
    (net (code "48") (name "Net-(U106C-~{RST})") (class "Default")
      (node (ref "R322") (pin "1") (pinfunction "1_1") (pintype "passive"))
      (node (ref "R323") (pin "1") (pinfunction "1_1") (pintype "passive"))
      (node (ref "R324") (pin "1") (pinfunction "1_1") (pintype "passive"))
      (node (ref "U106") (pin "70") (pinfunction "~{RST}_70") (pintype "passive"))
    )
    (net (code "49") (name "VCC3V3_XDS") (class "Default")
      (node (ref "C249") (pin "1") (pinfunction "1_1") (pintype "passive"))
      (node (ref "C251") (pin "1") (pinfunction "1_1") (pintype "passive"))
      (node (ref "C621") (pin "1") (pinfunction "1_1") (pintype "passive"))
      (node (ref "C642") (pin "1") (pinfunction "1_1") (pintype "passive"))
      (node (ref "C646") (pin "1") (pinfunction "1_1") (pintype "passive"))
      (node (ref "C647") (pin "1") (pinfunction "1_1") (pintype "passive"))
      (node (ref "C650") (pin "1") (pinfunction "1_1") (pintype "passive"))
      (node (ref "C657") (pin "1") (pinfunction "1_1") (pintype "passive"))
      (node (ref "C660") (pin "1") (pinfunction "1_1") (pintype "passive"))
      (node (ref "C668") (pin "1") (pinfunction "1_1") (pintype "passive"))
      (node (ref "C669") (pin "1") (pinfunction "1_1") (pintype "passive"))
      (node (ref "J34") (pin "5") (pinfunction "5_5") (pintype "passive"))
      (node (ref "J40") (pin "1") (pinfunction "1_1") (pintype "passive"))
      (node (ref "R313") (pin "2") (pinfunction "2_2") (pintype "passive"))
      (node (ref "R314") (pin "2") (pinfunction "2_2") (pintype "passive"))
      (node (ref "R322") (pin "2") (pinfunction "2_2") (pintype "passive"))
      (node (ref "R334") (pin "1") (pinfunction "1_1") (pintype "passive"))
      (node (ref "R649") (pin "2") (pinfunction "2_2") (pintype "passive"))
      (node (ref "R651") (pin "2") (pinfunction "2_2") (pintype "passive"))
      (node (ref "R654") (pin "1") (pinfunction "1_1") (pintype "passive"))
      (node (ref "R655") (pin "1") (pinfunction "1_1") (pintype "passive"))
      (node (ref "R657") (pin "2") (pinfunction "2_2") (pintype "passive"))
      (node (ref "R663") (pin "1") (pinfunction "1_1") (pintype "passive"))
      (node (ref "U106") (pin "101") (pinfunction "VDD_101") (pintype "power_in"))
      (node (ref "U106") (pin "113") (pinfunction "VDD_113") (pintype "power_in"))
      (node (ref "U106") (pin "122") (pinfunction "VDD_122") (pintype "power_in"))
      (node (ref "U106") (pin "16") (pinfunction "VDD_16") (pintype "power_in"))
      (node (ref "U106") (pin "26") (pinfunction "VDD_26") (pintype "power_in"))
      (node (ref "U106") (pin "28") (pinfunction "VDD_28") (pintype "power_in"))
      (node (ref "U106") (pin "39") (pinfunction "VDD_39") (pintype "power_in"))
      (node (ref "U106") (pin "47") (pinfunction "VDD_47") (pintype "power_in"))
      (node (ref "U106") (pin "51") (pinfunction "VDD_51") (pintype "power_in"))
      (node (ref "U106") (pin "52") (pinfunction "VDD_52") (pintype "power_in"))
      (node (ref "U106") (pin "69") (pinfunction "VDD_69") (pintype "power_in"))
      (node (ref "U106") (pin "7") (pinfunction "VDD_7") (pintype "power_in"))
      (node (ref "U106") (pin "79") (pinfunction "VDD_79") (pintype "power_in"))
      (node (ref "U106") (pin "8") (pinfunction "VDDA_8") (pintype "power_in"))
      (node (ref "U106") (pin "90") (pinfunction "VDD_90") (pintype "power_in"))
      (node (ref "U57") (pin "3") (pinfunction "OUT1_3") (pintype "output"))
      (node (ref "U57") (pin "4") (pinfunction "OUT2_4") (pintype "output"))
    )
    (net (code "50") (name "XDS_SHIELD") (class "Default")
      (node (ref "FL6") (pin "1") (pinfunction "1_1") (pintype "passive"))
      (node (ref "J23") (pin "SH1") (pinfunction "SH1_SH1") (pintype "passive"))
      (node (ref "J23") (pin "SH2") (pinfunction "SH2_SH2") (pintype "passive"))
      (node (ref "J23") (pin "SH3") (pinfunction "SH3_SH3") (pintype "passive"))
      (node (ref "J23") (pin "SH4") (pinfunction "SH4_SH4") (pintype "passive"))
      (node (ref "J23") (pin "SH5") (pinfunction "SH5_SH5") (pintype "passive"))
      (node (ref "J23") (pin "SH6") (pinfunction "SH6_SH6") (pintype "passive"))
    )
    (net (code "51") (name "XDS_USB_VBUS") (class "Default")
      (node (ref "C250") (pin "1") (pinfunction "1_1") (pintype "passive"))
      (node (ref "J23") (pin "1") (pinfunction "VBUS_1") (pintype "passive"))
      (node (ref "R670") (pin "1") (pinfunction "1_1") (pintype "passive"))
      (node (ref "R678") (pin "1") (pinfunction "1_1") (pintype "passive"))
      (node (ref "U57") (pin "1") (pinfunction "IN1_1") (pintype "input"))
      (node (ref "U57") (pin "2") (pinfunction "IN2_2") (pintype "input"))
      (node (ref "U57") (pin "8") (pinfunction "EN_8") (pintype "passive"))
      (node (ref "U58") (pin "6") (pinfunction "VCC_6") (pintype "power_in"))
    )
    (net (code "52") (name "unconnected-(J34-Pad6)") (class "Default")
      (node (ref "J34") (pin "6") (pinfunction "6_6") (pintype "passive+no_connect"))
    )
    (net (code "53") (name "unconnected-(J34-Pad13)") (class "Default")
      (node (ref "J34") (pin "13") (pinfunction "13_13") (pintype "passive+no_connect"))
    )
    (net (code "54") (name "unconnected-(J34-Pad14)") (class "Default")
      (node (ref "J34") (pin "14") (pinfunction "14_14") (pintype "passive+no_connect"))
    )
    (net (code "55") (name "unconnected-(J34-Pad15)") (class "Default")
      (node (ref "J34") (pin "15") (pinfunction "15_15") (pintype "passive+no_connect"))
    )
    (net (code "56") (name "unconnected-(J34-Pad17)") (class "Default")
      (node (ref "J34") (pin "17") (pinfunction "17_17") (pintype "passive+no_connect"))
    )
    (net (code "57") (name "unconnected-(J34-Pad18)") (class "Default")
      (node (ref "J34") (pin "18") (pinfunction "18_18") (pintype "passive+no_connect"))
    )
    (net (code "58") (name "unconnected-(J34-Pad19)") (class "Default")
      (node (ref "J34") (pin "19") (pinfunction "19_19") (pintype "passive+no_connect"))
    )
    (net (code "59") (name "unconnected-(J40-Pad7)") (class "Default")
      (node (ref "J40") (pin "7") (pinfunction "7_7") (pintype "passive+no_connect"))
    )
    (net (code "60") (name "unconnected-(U57-NC-Pad7)") (class "Default")
      (node (ref "U57") (pin "7") (pinfunction "NC_7") (pintype "passive+no_connect"))
    )
    (net (code "61") (name "unconnected-(U58-IO1-Pad1)") (class "Default")
      (node (ref "U58") (pin "1") (pinfunction "IO1_1") (pintype "passive+no_connect"))
    )
    (net (code "62") (name "unconnected-(U106A-PA0{slash}U0RX-Pad33)") (class "Default")
      (node (ref "U106") (pin "33") (pinfunction "PA0/U0RX_33") (pintype "bidirectional+no_connect"))
    )
    (net (code "63") (name "unconnected-(U106A-PA1{slash}U0TX-Pad34)") (class "Default")
      (node (ref "U106") (pin "34") (pinfunction "PA1/U0TX_34") (pintype "bidirectional+no_connect"))
    )
    (net (code "64") (name "unconnected-(U106A-PA7-Pad41)") (class "Default")
      (node (ref "U106") (pin "41") (pinfunction "PA7_41") (pintype "bidirectional+no_connect"))
    )
    (net (code "65") (name "unconnected-(U106A-PB2{slash}I2C0SCL-Pad91)") (class "Default")
      (node (ref "U106") (pin "91") (pinfunction "PB2/I2C0SCL_91") (pintype "bidirectional+no_connect"))
    )
    (net (code "66") (name "unconnected-(U106A-PB3{slash}I2C0SDA-Pad92)") (class "Default")
      (node (ref "U106") (pin "92") (pinfunction "PB3/I2C0SDA_92") (pintype "bidirectional+no_connect"))
    )
    (net (code "67") (name "unconnected-(U106A-PB4{slash}AIN10-Pad121)") (class "Default")
      (node (ref "U106") (pin "121") (pinfunction "PB4/AIN10_121") (pintype "bidirectional+no_connect"))
    )
    (net (code "68") (name "unconnected-(U106A-PB5{slash}AIN11-Pad120)") (class "Default")
      (node (ref "U106") (pin "120") (pinfunction "PB5/AIN11_120") (pintype "bidirectional+no_connect"))
    )
    (net (code "69") (name "unconnected-(U106A-PC4{slash}C1--Pad25)") (class "Default")
      (node (ref "U106") (pin "25") (pinfunction "PC4/C1-_25") (pintype "bidirectional+no_connect"))
    )
    (net (code "70") (name "unconnected-(U106A-PC5{slash}C1+-Pad24)") (class "Default")
      (node (ref "U106") (pin "24") (pinfunction "PC5/C1+_24") (pintype "bidirectional+no_connect"))
    )
    (net (code "71") (name "unconnected-(U106A-PC6{slash}C0+-Pad23)") (class "Default")
      (node (ref "U106") (pin "23") (pinfunction "PC6/C0+_23") (pintype "bidirectional+no_connect"))
    )
    (net (code "72") (name "unconnected-(U106A-PC7{slash}C0--Pad22)") (class "Default")
      (node (ref "U106") (pin "22") (pinfunction "PC7/C0-_22") (pintype "bidirectional+no_connect"))
    )
    (net (code "73") (name "unconnected-(U106A-PD1{slash}AIN14-Pad2)") (class "Default")
      (node (ref "U106") (pin "2") (pinfunction "PD1/AIN14_2") (pintype "bidirectional+no_connect"))
    )
    (net (code "74") (name "unconnected-(U106A-PD4{slash}AIN7-Pad125)") (class "Default")
      (node (ref "U106") (pin "125") (pinfunction "PD4/AIN7_125") (pintype "bidirectional+no_connect"))
    )
    (net (code "75") (name "unconnected-(U106A-PD5{slash}AIN6-Pad126)") (class "Default")
      (node (ref "U106") (pin "126") (pinfunction "PD5/AIN6_126") (pintype "bidirectional+no_connect"))
    )
    (net (code "76") (name "unconnected-(U106A-PD6{slash}AIN5-Pad127)") (class "Default")
      (node (ref "U106") (pin "127") (pinfunction "PD6/AIN5_127") (pintype "bidirectional+no_connect"))
    )
    (net (code "77") (name "unconnected-(U106A-PD7{slash}AIN4-Pad128)") (class "Default")
      (node (ref "U106") (pin "128") (pinfunction "PD7/AIN4_128") (pintype "bidirectional+no_connect"))
    )
    (net (code "78") (name "unconnected-(U106A-PE0{slash}AIN3-Pad15)") (class "Default")
      (node (ref "U106") (pin "15") (pinfunction "PE0/AIN3_15") (pintype "bidirectional+no_connect"))
    )
    (net (code "79") (name "unconnected-(U106A-PE1{slash}AIN2-Pad14)") (class "Default")
      (node (ref "U106") (pin "14") (pinfunction "PE1/AIN2_14") (pintype "bidirectional+no_connect"))
    )
    (net (code "80") (name "unconnected-(U106A-PE2{slash}AIN1-Pad13)") (class "Default")
      (node (ref "U106") (pin "13") (pinfunction "PE2/AIN1_13") (pintype "bidirectional+no_connect"))
    )
    (net (code "81") (name "unconnected-(U106A-PE3{slash}AIN0-Pad12)") (class "Default")
      (node (ref "U106") (pin "12") (pinfunction "PE3/AIN0_12") (pintype "bidirectional+no_connect"))
    )
    (net (code "82") (name "unconnected-(U106A-PE4{slash}AIN9-Pad123)") (class "Default")
      (node (ref "U106") (pin "123") (pinfunction "PE4/AIN9_123") (pintype "bidirectional+no_connect"))
    )
    (net (code "83") (name "unconnected-(U106A-PE5{slash}AIN8-Pad124)") (class "Default")
      (node (ref "U106") (pin "124") (pinfunction "PE5/AIN8_124") (pintype "bidirectional+no_connect"))
    )
    (net (code "84") (name "unconnected-(U106A-PF2-Pad44)") (class "Default")
      (node (ref "U106") (pin "44") (pinfunction "PF2_44") (pintype "bidirectional+no_connect"))
    )
    (net (code "85") (name "unconnected-(U106A-PF3-Pad45)") (class "Default")
      (node (ref "U106") (pin "45") (pinfunction "PF3_45") (pintype "bidirectional+no_connect"))
    )
    (net (code "86") (name "unconnected-(U106A-PF4-Pad46)") (class "Default")
      (node (ref "U106") (pin "46") (pinfunction "PF4_46") (pintype "bidirectional+no_connect"))
    )
    (net (code "87") (name "unconnected-(U106A-PG0-Pad49)") (class "Default")
      (node (ref "U106") (pin "49") (pinfunction "PG0_49") (pintype "bidirectional+no_connect"))
    )
    (net (code "88") (name "unconnected-(U106A-PG1-Pad50)") (class "Default")
      (node (ref "U106") (pin "50") (pinfunction "PG1_50") (pintype "bidirectional+no_connect"))
    )
    (net (code "89") (name "unconnected-(U106A-PH0-Pad29)") (class "Default")
      (node (ref "U106") (pin "29") (pinfunction "PH0_29") (pintype "bidirectional+no_connect"))
    )
    (net (code "90") (name "unconnected-(U106A-PH1-Pad30)") (class "Default")
      (node (ref "U106") (pin "30") (pinfunction "PH1_30") (pintype "bidirectional+no_connect"))
    )
    (net (code "91") (name "unconnected-(U106A-PH2-Pad31)") (class "Default")
      (node (ref "U106") (pin "31") (pinfunction "PH2_31") (pintype "bidirectional+no_connect"))
    )
    (net (code "92") (name "unconnected-(U106A-PH3-Pad32)") (class "Default")
      (node (ref "U106") (pin "32") (pinfunction "PH3_32") (pintype "bidirectional+no_connect"))
    )
    (net (code "93") (name "unconnected-(U106A-PJ0-Pad116)") (class "Default")
      (node (ref "U106") (pin "116") (pinfunction "PJ0_116") (pintype "bidirectional+no_connect"))
    )
    (net (code "94") (name "unconnected-(U106A-PJ1-Pad117)") (class "Default")
      (node (ref "U106") (pin "117") (pinfunction "PJ1_117") (pintype "bidirectional+no_connect"))
    )
    (net (code "95") (name "unconnected-(U106A-PK0{slash}AIN16-Pad18)") (class "Default")
      (node (ref "U106") (pin "18") (pinfunction "PK0/AIN16_18") (pintype "bidirectional+no_connect"))
    )
    (net (code "96") (name "unconnected-(U106A-PK1{slash}AIN17-Pad19)") (class "Default")
      (node (ref "U106") (pin "19") (pinfunction "PK1/AIN17_19") (pintype "bidirectional+no_connect"))
    )
    (net (code "97") (name "unconnected-(U106A-PK2{slash}AIN18-Pad20)") (class "Default")
      (node (ref "U106") (pin "20") (pinfunction "PK2/AIN18_20") (pintype "bidirectional+no_connect"))
    )
    (net (code "98") (name "unconnected-(U106A-PK3{slash}AIN19-Pad21)") (class "Default")
      (node (ref "U106") (pin "21") (pinfunction "PK3/AIN19_21") (pintype "bidirectional+no_connect"))
    )
    (net (code "99") (name "unconnected-(U106A-PL0-Pad81)") (class "Default")
      (node (ref "U106") (pin "81") (pinfunction "PL0_81") (pintype "bidirectional+no_connect"))
    )
    (net (code "100") (name "unconnected-(U106A-PL1-Pad82)") (class "Default")
      (node (ref "U106") (pin "82") (pinfunction "PL1_82") (pintype "bidirectional+no_connect"))
    )
    (net (code "101") (name "unconnected-(U106A-PL2-Pad83)") (class "Default")
      (node (ref "U106") (pin "83") (pinfunction "PL2_83") (pintype "bidirectional+no_connect"))
    )
    (net (code "102") (name "unconnected-(U106A-PL3-Pad84)") (class "Default")
      (node (ref "U106") (pin "84") (pinfunction "PL3_84") (pintype "bidirectional+no_connect"))
    )
    (net (code "103") (name "unconnected-(U106A-PL4-Pad85)") (class "Default")
      (node (ref "U106") (pin "85") (pinfunction "PL4_85") (pintype "bidirectional+no_connect"))
    )
    (net (code "104") (name "unconnected-(U106A-PL5-Pad86)") (class "Default")
      (node (ref "U106") (pin "86") (pinfunction "PL5_86") (pintype "bidirectional+no_connect"))
    )
    (net (code "105") (name "unconnected-(U106A-PM0-Pad78)") (class "Default")
      (node (ref "U106") (pin "78") (pinfunction "PM0_78") (pintype "bidirectional+no_connect"))
    )
    (net (code "106") (name "unconnected-(U106A-PM1-Pad77)") (class "Default")
      (node (ref "U106") (pin "77") (pinfunction "PM1_77") (pintype "bidirectional+no_connect"))
    )
    (net (code "107") (name "unconnected-(U106A-PM2-Pad76)") (class "Default")
      (node (ref "U106") (pin "76") (pinfunction "PM2_76") (pintype "bidirectional+no_connect"))
    )
    (net (code "108") (name "unconnected-(U106A-PM3-Pad75)") (class "Default")
      (node (ref "U106") (pin "75") (pinfunction "PM3_75") (pintype "bidirectional+no_connect"))
    )
    (net (code "109") (name "unconnected-(U106A-PM4-Pad74)") (class "Default")
      (node (ref "U106") (pin "74") (pinfunction "PM4_74") (pintype "bidirectional+no_connect"))
    )
    (net (code "110") (name "unconnected-(U106A-PM5-Pad73)") (class "Default")
      (node (ref "U106") (pin "73") (pinfunction "PM5_73") (pintype "bidirectional+no_connect"))
    )
    (net (code "111") (name "unconnected-(U106A-PM6-Pad72)") (class "Default")
      (node (ref "U106") (pin "72") (pinfunction "PM6_72") (pintype "bidirectional+no_connect"))
    )
    (net (code "112") (name "unconnected-(U106A-PM7-Pad71)") (class "Default")
      (node (ref "U106") (pin "71") (pinfunction "PM7_71") (pintype "bidirectional+no_connect"))
    )
    (net (code "113") (name "unconnected-(U106A-PN0-Pad107)") (class "Default")
      (node (ref "U106") (pin "107") (pinfunction "PN0_107") (pintype "bidirectional+no_connect"))
    )
    (net (code "114") (name "unconnected-(U106A-PN1-Pad108)") (class "Default")
      (node (ref "U106") (pin "108") (pinfunction "PN1_108") (pintype "bidirectional+no_connect"))
    )
    (net (code "115") (name "unconnected-(U106A-PN2-Pad109)") (class "Default")
      (node (ref "U106") (pin "109") (pinfunction "PN2_109") (pintype "bidirectional+no_connect"))
    )
    (net (code "116") (name "unconnected-(U106A-PN3-Pad110)") (class "Default")
      (node (ref "U106") (pin "110") (pinfunction "PN3_110") (pintype "bidirectional+no_connect"))
    )
    (net (code "117") (name "unconnected-(U106A-PN4-Pad111)") (class "Default")
      (node (ref "U106") (pin "111") (pinfunction "PN4_111") (pintype "bidirectional+no_connect"))
    )
    (net (code "118") (name "unconnected-(U106A-PN5-Pad112)") (class "Default")
      (node (ref "U106") (pin "112") (pinfunction "PN5_112") (pintype "bidirectional+no_connect"))
    )
    (net (code "119") (name "unconnected-(U106A-PP0{slash}C2+-Pad118)") (class "Default")
      (node (ref "U106") (pin "118") (pinfunction "PP0/C2+_118") (pintype "bidirectional+no_connect"))
    )
    (net (code "120") (name "unconnected-(U106A-PP1{slash}C2--Pad119)") (class "Default")
      (node (ref "U106") (pin "119") (pinfunction "PP1/C2-_119") (pintype "bidirectional+no_connect"))
    )
    (net (code "121") (name "unconnected-(U106A-PP2-Pad103)") (class "Default")
      (node (ref "U106") (pin "103") (pinfunction "PP2_103") (pintype "bidirectional+no_connect"))
    )
    (net (code "122") (name "unconnected-(U106A-PP3-Pad104)") (class "Default")
      (node (ref "U106") (pin "104") (pinfunction "PP3_104") (pintype "bidirectional+no_connect"))
    )
    (net (code "123") (name "unconnected-(U106A-PP4-Pad105)") (class "Default")
      (node (ref "U106") (pin "105") (pinfunction "PP4_105") (pintype "bidirectional+no_connect"))
    )
    (net (code "124") (name "unconnected-(U106A-PP5-Pad106)") (class "Default")
      (node (ref "U106") (pin "106") (pinfunction "PP5_106") (pintype "bidirectional+no_connect"))
    )
    (net (code "125") (name "unconnected-(U106A-PQ0-Pad5)") (class "Default")
      (node (ref "U106") (pin "5") (pinfunction "PQ0_5") (pintype "bidirectional+no_connect"))
    )
    (net (code "126") (name "unconnected-(U106A-PQ1-Pad6)") (class "Default")
      (node (ref "U106") (pin "6") (pinfunction "PQ1_6") (pintype "bidirectional+no_connect"))
    )
    (net (code "127") (name "unconnected-(U106A-PQ2-Pad11)") (class "Default")
      (node (ref "U106") (pin "11") (pinfunction "PQ2_11") (pintype "bidirectional+no_connect"))
    )
    (net (code "128") (name "unconnected-(U106A-PQ3-Pad27)") (class "Default")
      (node (ref "U106") (pin "27") (pinfunction "PQ3_27") (pintype "bidirectional+no_connect"))
    )
    (net (code "129") (name "unconnected-(U106A-PQ4-Pad102)") (class "Default")
      (node (ref "U106") (pin "102") (pinfunction "PQ4_102") (pintype "bidirectional+no_connect"))
    )
    (net (code "130") (name "unconnected-(U106C-EN0RX0N-Pad56)") (class "Default")
      (node (ref "U106") (pin "56") (pinfunction "EN0RX0N_56") (pintype "passive+no_connect"))
    )
    (net (code "131") (name "unconnected-(U106C-EN0RX0P-Pad57)") (class "Default")
      (node (ref "U106") (pin "57") (pinfunction "EN0RX0P_57") (pintype "passive+no_connect"))
    )
    (net (code "132") (name "unconnected-(U106C-EN0RXIN-Pad53)") (class "Default")
      (node (ref "U106") (pin "53") (pinfunction "EN0RXIN_53") (pintype "passive+no_connect"))
    )
    (net (code "133") (name "unconnected-(U106C-EN0RXIP-Pad54)") (class "Default")
      (node (ref "U106") (pin "54") (pinfunction "EN0RXIP_54") (pintype "passive+no_connect"))
    )
    (net (code "134") (name "unconnected-(U106C-XOSC1-Pad67)") (class "Default")
      (node (ref "U106") (pin "67") (pinfunction "XOSC1_67") (pintype "output+no_connect"))
    )
    (net (code "135") (name "unconnected-(U106C-~{HIB}-Pad65)") (class "Default")
      (node (ref "U106") (pin "65") (pinfunction "~{HIB}_65") (pintype "passive+no_connect"))
    )
    (net (code "136") (name "unconnected-(U107-NC1-Pad2)") (class "Default")
      (node (ref "U107") (pin "2") (pinfunction "NC1_2") (pintype "passive+no_connect"))
    )
    (net (code "137") (name "unconnected-(U107-NC2-Pad4)") (class "Default")
      (node (ref "U107") (pin "4") (pinfunction "NC2_4") (pintype "passive+no_connect"))
    )
    (net (code "138") (name "unconnected-(U107-NC3-Pad5)") (class "Default")
      (node (ref "U107") (pin "5") (pinfunction "NC3_5") (pintype "passive+no_connect"))
    )
  )
)
